# Modellfinder.net
KiCad netlist of a schematic drawn in EAGLE
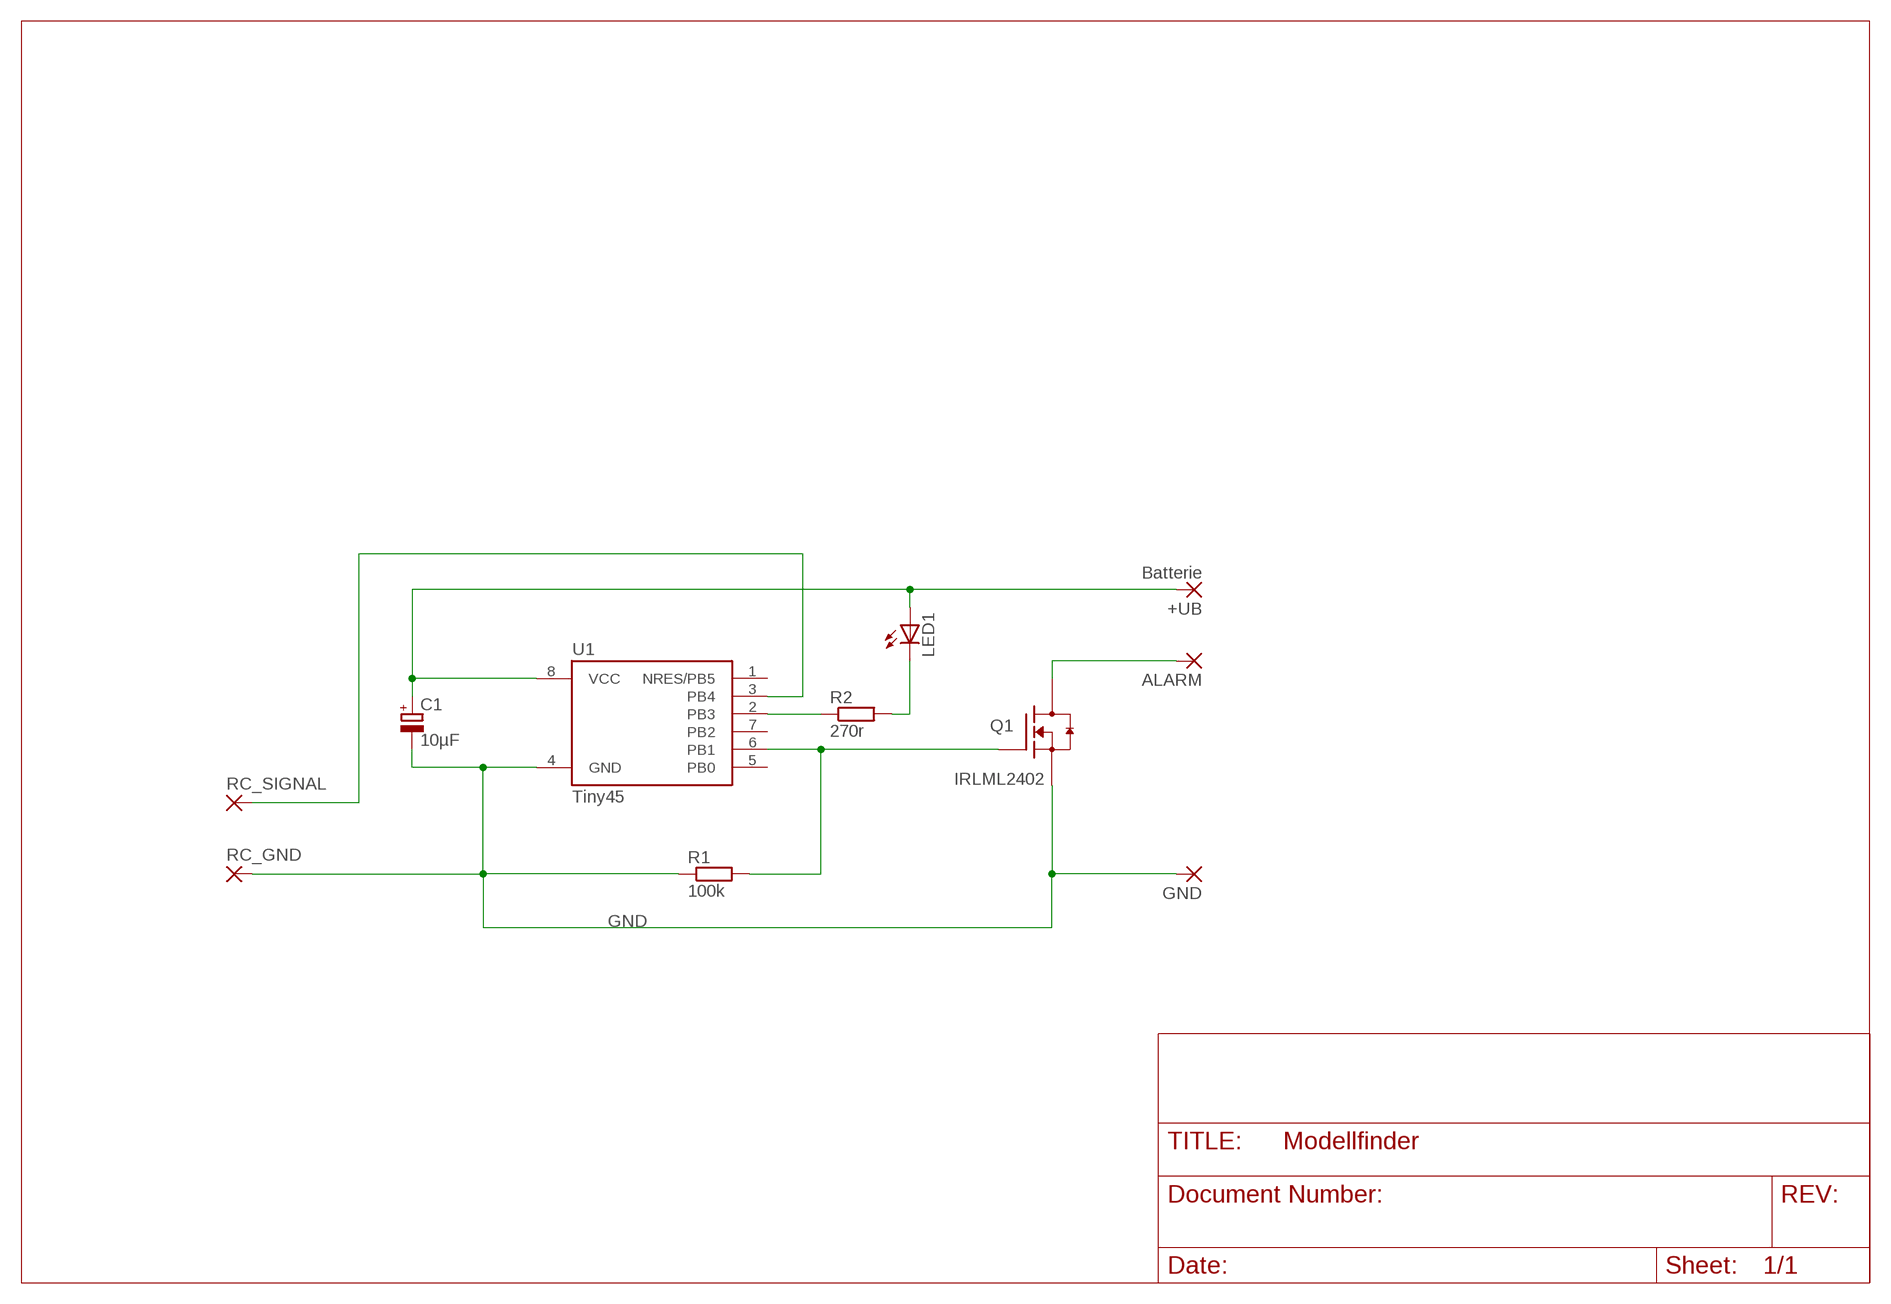
[diagram p0: schematic, sheet 1]

(export (version "E")
  (design (tool "Eeschema 10.0.6"))
  (components
    (comp (ref "+UB")
      (value "Batterie")
      (footprint "eagle-import:SMD1,27-2,54")
      (libsource (lib "eagle-import") (part "SMD2"))
    )
    (comp (ref "ALARM")
      (value "SMD2")
      (footprint "eagle-import:SMD1,27-2,54")
      (libsource (lib "eagle-import") (part "SMD2"))
    )
    (comp (ref "C1")
      (value "10µF")
      (footprint "eagle-import:085CS_1AR")
      (libsource (lib "eagle-import") (part "CPOL-EU085CS-1AR"))
    )
    (comp (ref "GND")
      (value "SMD2")
      (footprint "eagle-import:SMD1,27-2,54")
      (libsource (lib "eagle-import") (part "SMD2"))
    )
    (comp (ref "LED1")
      (value "LEDSML0805")
      (footprint "eagle-import:SML0805")
      (libsource (lib "eagle-import") (part "LEDSML0805"))
    )
    (comp (ref "Q1")
      (value "IRLML2402")
      (footprint "eagle-import:SOT95P280X135-3N")
      (libsource (lib "eagle-import") (part "MOSFET-NCH_SOT-23"))
    )
    (comp (ref "R1")
      (value "100k")
      (footprint "eagle-import:M1206")
      (libsource (lib "eagle-import") (part "R-EU_M1206"))
    )
    (comp (ref "R2")
      (value "270r")
      (footprint "eagle-import:M1206")
      (libsource (lib "eagle-import") (part "R-EU_M1206"))
    )
    (comp (ref "RC_GND")
      (value "SMD2")
      (footprint "eagle-import:SMD1,27-2,54")
      (libsource (lib "eagle-import") (part "SMD2"))
    )
    (comp (ref "RC_SIGNAL")
      (value "SMD2")
      (footprint "eagle-import:SMD1,27-2,54")
      (libsource (lib "eagle-import") (part "SMD2"))
    )
    (comp (ref "U1")
      (value "Tiny45")
      (footprint "eagle-import:SOIC8_EIAJ_208MIL")
      (libsource (lib "eagle-import") (part "ATTINY85S-"))
    )
  )
  (nets
    (net (code "1") (name "/GND") (class "Default")
      (node (ref "C1") (pin "-") (pinfunction "-_-") (pintype "passive"))
      (node (ref "GND") (pin "1") (pinfunction "P_1") (pintype "passive"))
      (node (ref "Q1") (pin "2") (pinfunction "S_2") (pintype "passive"))
      (node (ref "R1") (pin "1") (pinfunction "1_1") (pintype "passive"))
      (node (ref "RC_GND") (pin "1") (pinfunction "P_1") (pintype "passive"))
      (node (ref "U1") (pin "4") (pinfunction "GND_4") (pintype "power_in"))
    )
    (net (code "2") (name "Net-(+UB-P)") (class "Default")
      (node (ref "+UB") (pin "1") (pinfunction "P_1") (pintype "passive"))
      (node (ref "C1") (pin "+") (pinfunction "+_+") (pintype "passive"))
      (node (ref "LED1") (pin "A") (pinfunction "A_A") (pintype "passive"))
      (node (ref "U1") (pin "8") (pinfunction "VCC_8") (pintype "power_in"))
    )
    (net (code "3") (name "Net-(ALARM-P)") (class "Default")
      (node (ref "ALARM") (pin "1") (pinfunction "P_1") (pintype "passive"))
      (node (ref "Q1") (pin "3") (pinfunction "D_3") (pintype "passive"))
    )
    (net (code "4") (name "Net-(LED1-PadC)") (class "Default")
      (node (ref "LED1") (pin "C") (pinfunction "C_C") (pintype "passive"))
      (node (ref "R2") (pin "2") (pinfunction "2_2") (pintype "passive"))
    )
    (net (code "5") (name "Net-(Q1-G)") (class "Default")
      (node (ref "Q1") (pin "1") (pinfunction "G_1") (pintype "passive"))
      (node (ref "R1") (pin "2") (pinfunction "2_2") (pintype "passive"))
      (node (ref "U1") (pin "6") (pinfunction "PB1_6") (pintype "bidirectional"))
    )
    (net (code "6") (name "Net-(RC_SIGNAL-P)") (class "Default")
      (node (ref "RC_SIGNAL") (pin "1") (pinfunction "P_1") (pintype "passive"))
      (node (ref "U1") (pin "3") (pinfunction "PB4_3") (pintype "bidirectional"))
    )
    (net (code "7") (name "Net-(U1-PB3)") (class "Default")
      (node (ref "R2") (pin "1") (pinfunction "1_1") (pintype "passive"))
      (node (ref "U1") (pin "2") (pinfunction "PB3_2") (pintype "bidirectional"))
    )
    (net (code "8") (name "unconnected-(U1-NRES{slash}PB5-Pad1)") (class "Default")
      (node (ref "U1") (pin "1") (pinfunction "NRES/PB5_1") (pintype "bidirectional"))
    )
    (net (code "9") (name "unconnected-(U1-PB0-Pad5)") (class "Default")
      (node (ref "U1") (pin "5") (pinfunction "PB0_5") (pintype "bidirectional"))
    )
    (net (code "10") (name "unconnected-(U1-PB2-Pad7)") (class "Default")
      (node (ref "U1") (pin "7") (pinfunction "PB2_7") (pintype "bidirectional"))
    )
  )
)
